# main.net
KiCad netlist of a schematic drawn in EAGLE
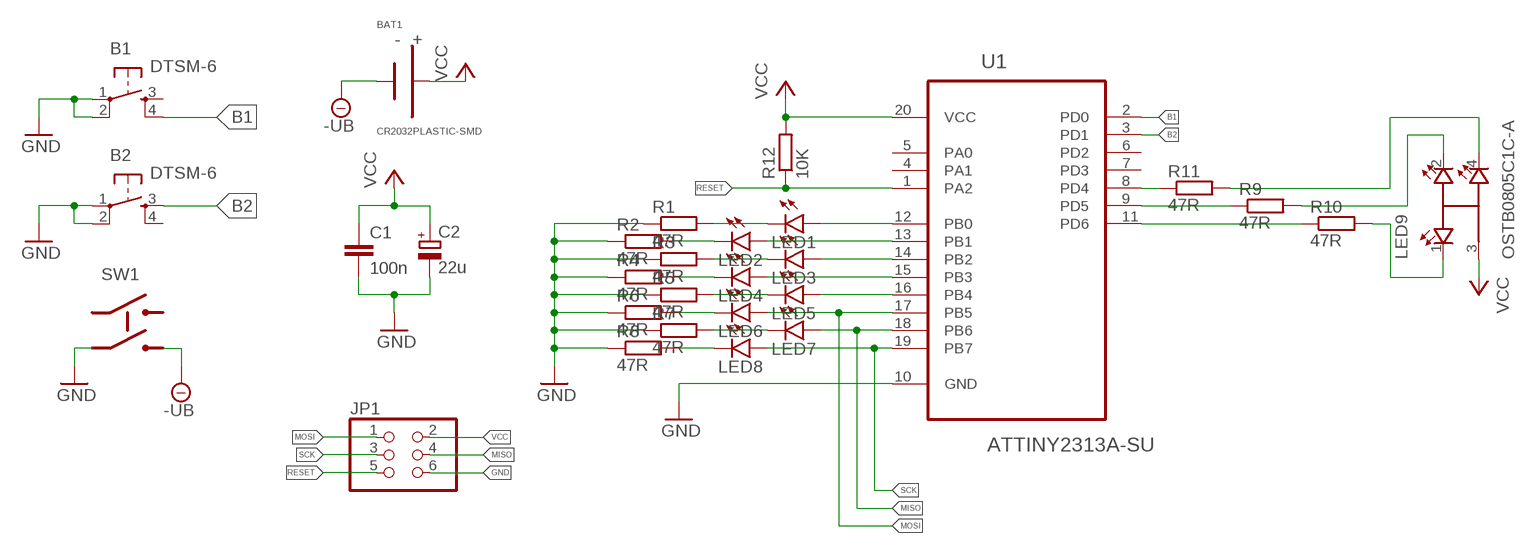
[diagram p0: schematic, sheet 1]

(export (version "E")
  (design (tool "Eeschema 10.0.6"))
  (components
    (comp (ref "B1")
      (value "DTSM-6")
      (footprint "eagle-import:DTSM-6")
      (libsource (lib "eagle-import") (part "DTSM-6"))
    )
    (comp (ref "B2")
      (value "DTSM-6")
      (footprint "eagle-import:DTSM-6")
      (libsource (lib "eagle-import") (part "DTSM-6"))
    )
    (comp (ref "BAT1")
      (value "CR2032PLASTIC-SMD")
      (footprint "eagle-import:BIG-SMD")
      (libsource (lib "eagle-import") (part "CR2032PLASTIC-SMD"))
    )
    (comp (ref "C1")
      (value "100n")
      (footprint "eagle-import:C0805")
      (libsource (lib "eagle-import") (part "C-EUC0805"))
    )
    (comp (ref "C2")
      (value "22u")
      (footprint "eagle-import:SMC_A")
      (libsource (lib "eagle-import") (part "CPOL-EUSMCA"))
    )
    (comp (ref "JP1")
      (value "PINHD-2X3")
      (footprint "eagle-import:2X03")
      (libsource (lib "eagle-import") (part "PINHD-2X3"))
    )
    (comp (ref "LED1")
      (value "LEDCHIP-LED0805")
      (footprint "eagle-import:CHIP-LED0805")
      (libsource (lib "eagle-import") (part "LEDCHIP-LED0805"))
    )
    (comp (ref "LED2")
      (value "LEDCHIP-LED0805")
      (footprint "eagle-import:CHIP-LED0805")
      (libsource (lib "eagle-import") (part "LEDCHIP-LED0805"))
    )
    (comp (ref "LED3")
      (value "LEDCHIP-LED0805")
      (footprint "eagle-import:CHIP-LED0805")
      (libsource (lib "eagle-import") (part "LEDCHIP-LED0805"))
    )
    (comp (ref "LED4")
      (value "LEDCHIP-LED0805")
      (footprint "eagle-import:CHIP-LED0805")
      (libsource (lib "eagle-import") (part "LEDCHIP-LED0805"))
    )
    (comp (ref "LED5")
      (value "LEDCHIP-LED0805")
      (footprint "eagle-import:CHIP-LED0805")
      (libsource (lib "eagle-import") (part "LEDCHIP-LED0805"))
    )
    (comp (ref "LED6")
      (value "LEDCHIP-LED0805")
      (footprint "eagle-import:CHIP-LED0805")
      (libsource (lib "eagle-import") (part "LEDCHIP-LED0805"))
    )
    (comp (ref "LED7")
      (value "LEDCHIP-LED0805")
      (footprint "eagle-import:CHIP-LED0805")
      (libsource (lib "eagle-import") (part "LEDCHIP-LED0805"))
    )
    (comp (ref "LED8")
      (value "LEDCHIP-LED0805")
      (footprint "eagle-import:CHIP-LED0805")
      (libsource (lib "eagle-import") (part "LEDCHIP-LED0805"))
    )
    (comp (ref "LED9")
      (value "OSTB0805C1C-A")
      (footprint "eagle-import:LEDSC200X125X110-4N")
      (fields (field (name "MF") "OptoSupply"))
      (libsource (lib "eagle-import") (part "OSTB0805C1C-A"))
    )
    (comp (ref "R1")
      (value "47R")
      (footprint "eagle-import:R0805")
      (libsource (lib "eagle-import") (part "R-EU_R0805"))
    )
    (comp (ref "R2")
      (value "47R")
      (footprint "eagle-import:R0805")
      (libsource (lib "eagle-import") (part "R-EU_R0805"))
    )
    (comp (ref "R3")
      (value "47R")
      (footprint "eagle-import:R0805")
      (libsource (lib "eagle-import") (part "R-EU_R0805"))
    )
    (comp (ref "R4")
      (value "47R")
      (footprint "eagle-import:R0805")
      (libsource (lib "eagle-import") (part "R-EU_R0805"))
    )
    (comp (ref "R5")
      (value "47R")
      (footprint "eagle-import:R0805")
      (libsource (lib "eagle-import") (part "R-EU_R0805"))
    )
    (comp (ref "R6")
      (value "47R")
      (footprint "eagle-import:R0805")
      (libsource (lib "eagle-import") (part "R-EU_R0805"))
    )
    (comp (ref "R7")
      (value "47R")
      (footprint "eagle-import:R0805")
      (libsource (lib "eagle-import") (part "R-EU_R0805"))
    )
    (comp (ref "R8")
      (value "47R")
      (footprint "eagle-import:R0805")
      (libsource (lib "eagle-import") (part "R-EU_R0805"))
    )
    (comp (ref "R9")
      (value "47R")
      (footprint "eagle-import:R0805")
      (libsource (lib "eagle-import") (part "R-EU_R0805"))
    )
    (comp (ref "R10")
      (value "47R")
      (footprint "eagle-import:R0805")
      (libsource (lib "eagle-import") (part "R-EU_R0805"))
    )
    (comp (ref "R11")
      (value "47R")
      (footprint "eagle-import:R0805")
      (libsource (lib "eagle-import") (part "R-EU_R0805"))
    )
    (comp (ref "R12")
      (value "10K")
      (footprint "eagle-import:R0805")
      (libsource (lib "eagle-import") (part "R-EU_R0805"))
    )
    (comp (ref "SW1")
      (value "MSS-22D18")
      (footprint "eagle-import:22D18")
      (libsource (lib "eagle-import") (part "MSS-22D18"))
    )
    (comp (ref "U1")
      (value "ATTINY2313A-SU")
      (footprint "eagle-import:SOIC127P1032X265-20N")
      (fields (field (name "MF") "Microchip"))
      (libsource (lib "eagle-import") (part "ATTINY2313A-SU"))
    )
  )
  (nets
    (net (code "1") (name "-UB") (class "Default")
      (node (ref "BAT1") (pin "1") (pinfunction "MIN_1") (pintype "power_in"))
      (node (ref "SW1") (pin "6") (pinfunction "OUT2_6") (pintype "passive"))
    )
    (net (code "2") (name "B1") (class "Default")
      (node (ref "B1") (pin "4") (pinfunction "4_4") (pintype "passive"))
      (node (ref "U1") (pin "2") (pinfunction "PD0_2") (pintype "bidirectional"))
    )
    (net (code "3") (name "B2") (class "Default")
      (node (ref "B2") (pin "3") (pinfunction "3_3") (pintype "passive"))
      (node (ref "U1") (pin "3") (pinfunction "PD1_3") (pintype "bidirectional"))
    )
    (net (code "4") (name "GND") (class "Default")
      (node (ref "B1") (pin "1") (pinfunction "1_1") (pintype "passive"))
      (node (ref "B1") (pin "2") (pinfunction "2_2") (pintype "passive"))
      (node (ref "B2") (pin "1") (pinfunction "1_1") (pintype "passive"))
      (node (ref "B2") (pin "2") (pinfunction "2_2") (pintype "passive"))
      (node (ref "C1") (pin "2") (pinfunction "2_2") (pintype "passive"))
      (node (ref "C2") (pin "-") (pinfunction "-_-") (pintype "passive"))
      (node (ref "JP1") (pin "6") (pinfunction "6_6") (pintype "passive"))
      (node (ref "R1") (pin "1") (pinfunction "1_1") (pintype "passive"))
      (node (ref "R2") (pin "1") (pinfunction "1_1") (pintype "passive"))
      (node (ref "R3") (pin "1") (pinfunction "1_1") (pintype "passive"))
      (node (ref "R4") (pin "1") (pinfunction "1_1") (pintype "passive"))
      (node (ref "R5") (pin "1") (pinfunction "1_1") (pintype "passive"))
      (node (ref "R6") (pin "1") (pinfunction "1_1") (pintype "passive"))
      (node (ref "R7") (pin "1") (pinfunction "1_1") (pintype "passive"))
      (node (ref "R8") (pin "1") (pinfunction "1_1") (pintype "passive"))
      (node (ref "SW1") (pin "5") (pinfunction "IN2_5") (pintype "passive"))
      (node (ref "U1") (pin "10") (pinfunction "GND_10") (pintype "passive"))
    )
    (net (code "5") (name "MISO") (class "Default")
      (node (ref "JP1") (pin "4") (pinfunction "4_4") (pintype "passive"))
      (node (ref "LED7") (pin "A") (pinfunction "A_A") (pintype "passive"))
      (node (ref "U1") (pin "18") (pinfunction "PB6_18") (pintype "bidirectional"))
    )
    (net (code "6") (name "MOSI") (class "Default")
      (node (ref "JP1") (pin "1") (pinfunction "1_1") (pintype "passive"))
      (node (ref "LED6") (pin "A") (pinfunction "A_A") (pintype "passive"))
      (node (ref "U1") (pin "17") (pinfunction "PB5_17") (pintype "bidirectional"))
    )
    (net (code "7") (name "Net-(LED1-PadC)") (class "Default")
      (node (ref "LED1") (pin "C") (pinfunction "C_C") (pintype "passive"))
      (node (ref "R1") (pin "2") (pinfunction "2_2") (pintype "passive"))
    )
    (net (code "8") (name "Net-(LED2-PadC)") (class "Default")
      (node (ref "LED2") (pin "C") (pinfunction "C_C") (pintype "passive"))
      (node (ref "R2") (pin "2") (pinfunction "2_2") (pintype "passive"))
    )
    (net (code "9") (name "Net-(LED3-PadC)") (class "Default")
      (node (ref "LED3") (pin "C") (pinfunction "C_C") (pintype "passive"))
      (node (ref "R3") (pin "2") (pinfunction "2_2") (pintype "passive"))
    )
    (net (code "10") (name "Net-(LED4-PadC)") (class "Default")
      (node (ref "LED4") (pin "C") (pinfunction "C_C") (pintype "passive"))
      (node (ref "R4") (pin "2") (pinfunction "2_2") (pintype "passive"))
    )
    (net (code "11") (name "Net-(LED5-PadC)") (class "Default")
      (node (ref "LED5") (pin "C") (pinfunction "C_C") (pintype "passive"))
      (node (ref "R5") (pin "2") (pinfunction "2_2") (pintype "passive"))
    )
    (net (code "12") (name "Net-(LED6-PadC)") (class "Default")
      (node (ref "LED6") (pin "C") (pinfunction "C_C") (pintype "passive"))
      (node (ref "R6") (pin "2") (pinfunction "2_2") (pintype "passive"))
    )
    (net (code "13") (name "Net-(LED7-PadC)") (class "Default")
      (node (ref "LED7") (pin "C") (pinfunction "C_C") (pintype "passive"))
      (node (ref "R7") (pin "2") (pinfunction "2_2") (pintype "passive"))
    )
    (net (code "14") (name "Net-(LED8-PadC)") (class "Default")
      (node (ref "LED8") (pin "C") (pinfunction "C_C") (pintype "passive"))
      (node (ref "R8") (pin "2") (pinfunction "2_2") (pintype "passive"))
    )
    (net (code "15") (name "Net-(LED9-Pad1)") (class "Default")
      (node (ref "LED9") (pin "1") (pinfunction "1_1") (pintype "passive"))
      (node (ref "R10") (pin "2") (pinfunction "2_2") (pintype "passive"))
    )
    (net (code "16") (name "Net-(LED9-Pad2)") (class "Default")
      (node (ref "LED9") (pin "2") (pinfunction "2_2") (pintype "passive"))
      (node (ref "R9") (pin "2") (pinfunction "2_2") (pintype "passive"))
    )
    (net (code "17") (name "Net-(LED9-Pad4)") (class "Default")
      (node (ref "LED9") (pin "4") (pinfunction "4_4") (pintype "passive"))
      (node (ref "R11") (pin "2") (pinfunction "2_2") (pintype "passive"))
    )
    (net (code "18") (name "Net-(U1-PB0)") (class "Default")
      (node (ref "LED1") (pin "A") (pinfunction "A_A") (pintype "passive"))
      (node (ref "U1") (pin "12") (pinfunction "PB0_12") (pintype "bidirectional"))
    )
    (net (code "19") (name "Net-(U1-PB1)") (class "Default")
      (node (ref "LED2") (pin "A") (pinfunction "A_A") (pintype "passive"))
      (node (ref "U1") (pin "13") (pinfunction "PB1_13") (pintype "bidirectional"))
    )
    (net (code "20") (name "Net-(U1-PB2)") (class "Default")
      (node (ref "LED3") (pin "A") (pinfunction "A_A") (pintype "passive"))
      (node (ref "U1") (pin "14") (pinfunction "PB2_14") (pintype "bidirectional"))
    )
    (net (code "21") (name "Net-(U1-PB3)") (class "Default")
      (node (ref "LED4") (pin "A") (pinfunction "A_A") (pintype "passive"))
      (node (ref "U1") (pin "15") (pinfunction "PB3_15") (pintype "bidirectional"))
    )
    (net (code "22") (name "Net-(U1-PB4)") (class "Default")
      (node (ref "LED5") (pin "A") (pinfunction "A_A") (pintype "passive"))
      (node (ref "U1") (pin "16") (pinfunction "PB4_16") (pintype "bidirectional"))
    )
    (net (code "23") (name "Net-(U1-PD4)") (class "Default")
      (node (ref "R11") (pin "1") (pinfunction "1_1") (pintype "passive"))
      (node (ref "U1") (pin "8") (pinfunction "PD4_8") (pintype "bidirectional"))
    )
    (net (code "24") (name "Net-(U1-PD5)") (class "Default")
      (node (ref "R9") (pin "1") (pinfunction "1_1") (pintype "passive"))
      (node (ref "U1") (pin "9") (pinfunction "PD5_9") (pintype "bidirectional"))
    )
    (net (code "25") (name "Net-(U1-PD6)") (class "Default")
      (node (ref "R10") (pin "1") (pinfunction "1_1") (pintype "passive"))
      (node (ref "U1") (pin "11") (pinfunction "PD6_11") (pintype "bidirectional"))
    )
    (net (code "26") (name "RESET") (class "Default")
      (node (ref "JP1") (pin "5") (pinfunction "5_5") (pintype "passive"))
      (node (ref "R12") (pin "1") (pinfunction "1_1") (pintype "passive"))
      (node (ref "U1") (pin "1") (pinfunction "PA2_1") (pintype "bidirectional"))
    )
    (net (code "27") (name "SCK") (class "Default")
      (node (ref "JP1") (pin "3") (pinfunction "3_3") (pintype "passive"))
      (node (ref "LED8") (pin "A") (pinfunction "A_A") (pintype "passive"))
      (node (ref "U1") (pin "19") (pinfunction "PB7_19") (pintype "bidirectional"))
    )
    (net (code "28") (name "VCC") (class "Default")
      (node (ref "BAT1") (pin "2") (pinfunction "PLUS_2") (pintype "power_in"))
      (node (ref "C1") (pin "1") (pinfunction "1_1") (pintype "passive"))
      (node (ref "C2") (pin "+") (pinfunction "+_+") (pintype "passive"))
      (node (ref "JP1") (pin "2") (pinfunction "2_2") (pintype "passive"))
      (node (ref "LED9") (pin "3") (pinfunction "3_3") (pintype "passive"))
      (node (ref "R12") (pin "2") (pinfunction "2_2") (pintype "passive"))
      (node (ref "U1") (pin "20") (pinfunction "VCC_20") (pintype "power_in"))
    )
    (net (code "29") (name "unconnected-(B1-Pad3)") (class "Default")
      (node (ref "B1") (pin "3") (pinfunction "3_3") (pintype "passive"))
    )
    (net (code "30") (name "unconnected-(B2-Pad4)") (class "Default")
      (node (ref "B2") (pin "4") (pinfunction "4_4") (pintype "passive"))
    )
    (net (code "31") (name "unconnected-(SW1-IN1-Pad2)") (class "Default")
      (node (ref "SW1") (pin "2") (pinfunction "IN1_2") (pintype "passive"))
    )
    (net (code "32") (name "unconnected-(SW1-OUT1-Pad3)") (class "Default")
      (node (ref "SW1") (pin "3") (pinfunction "OUT1_3") (pintype "passive"))
    )
    (net (code "33") (name "unconnected-(U1-PA0-Pad5)") (class "Default")
      (node (ref "U1") (pin "5") (pinfunction "PA0_5") (pintype "bidirectional"))
    )
    (net (code "34") (name "unconnected-(U1-PA1-Pad4)") (class "Default")
      (node (ref "U1") (pin "4") (pinfunction "PA1_4") (pintype "bidirectional"))
    )
    (net (code "35") (name "unconnected-(U1-PD2-Pad6)") (class "Default")
      (node (ref "U1") (pin "6") (pinfunction "PD2_6") (pintype "bidirectional"))
    )
    (net (code "36") (name "unconnected-(U1-PD3-Pad7)") (class "Default")
      (node (ref "U1") (pin "7") (pinfunction "PD3_7") (pintype "bidirectional"))
    )
  )
)
